# zxuno.net
KiCad netlist of a schematic drawn in EAGLE
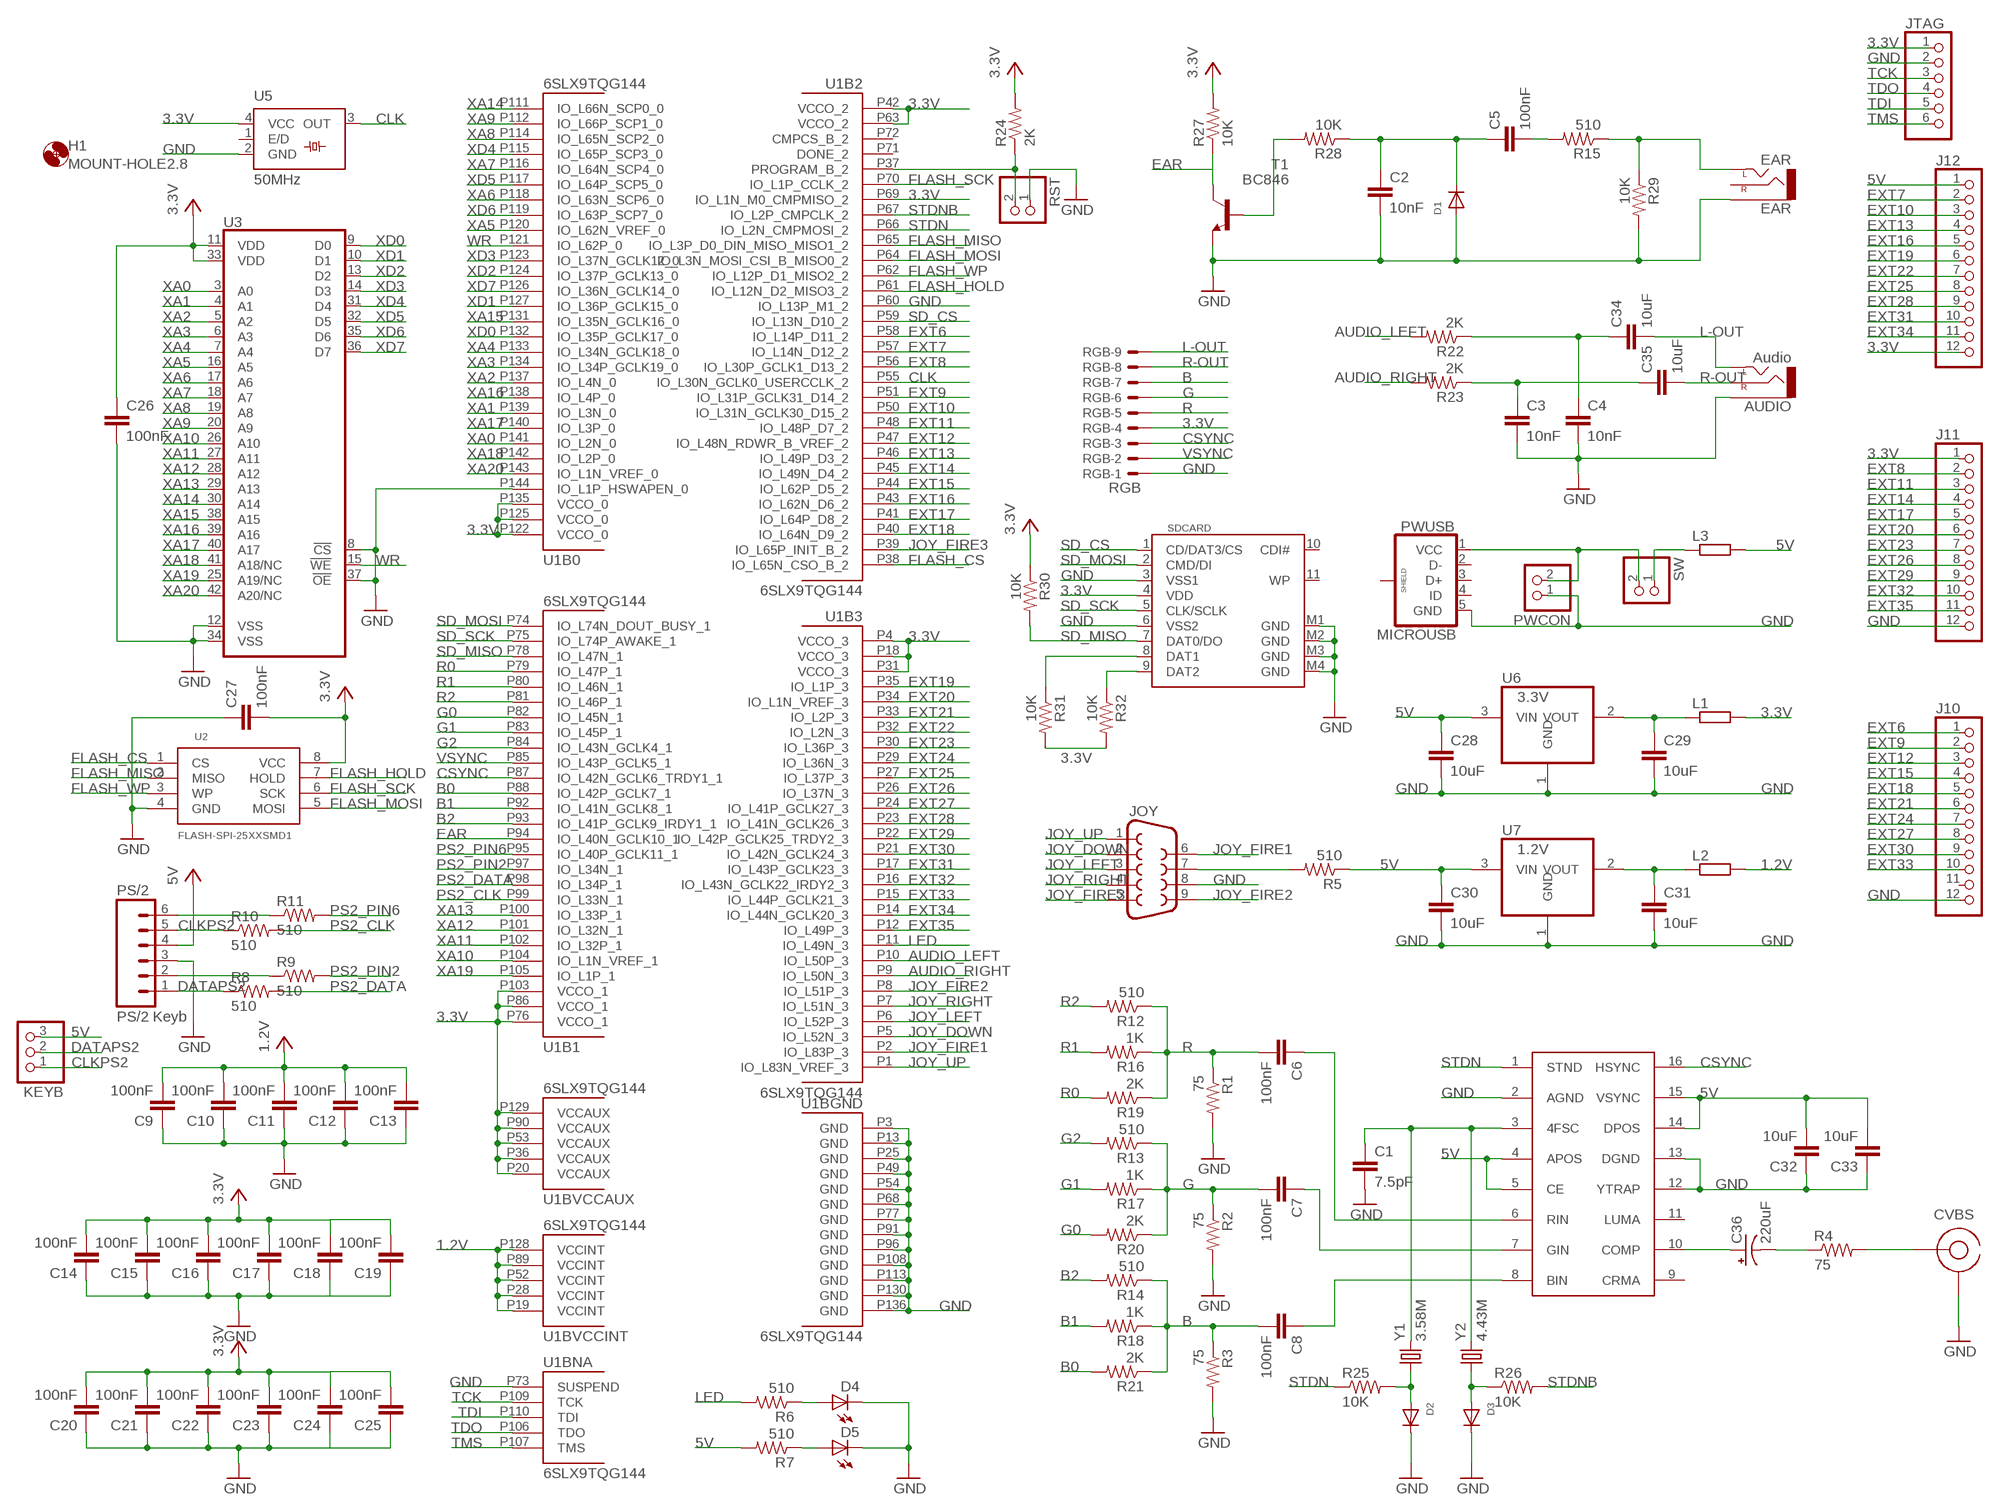
[diagram p0: schematic, sheet 1]

(export (version "E")
  (design (tool "Eeschema 10.0.6"))
  (components
    (comp (ref "AUDIO")
      (value "Audio")
      (footprint "eagle-import:AUDIO-JACK")
      (libsource (lib "eagle-import") (part "AUDIO-JACKPTH"))
    )
    (comp (ref "C1")
      (value "7.5pF")
      (footprint "eagle-import:C0805")
      (libsource (lib "eagle-import") (part "C-EUC0805"))
    )
    (comp (ref "C2")
      (value "10nF")
      (footprint "eagle-import:C0805")
      (libsource (lib "eagle-import") (part "C-EUC0805"))
    )
    (comp (ref "C3")
      (value "10nF")
      (footprint "eagle-import:C0805")
      (libsource (lib "eagle-import") (part "C-EUC0805"))
    )
    (comp (ref "C4")
      (value "10nF")
      (footprint "eagle-import:C0805")
      (libsource (lib "eagle-import") (part "C-EUC0805"))
    )
    (comp (ref "C5")
      (value "100nF")
      (footprint "eagle-import:C0603")
      (libsource (lib "eagle-import") (part "C-EUC0603"))
    )
    (comp (ref "C6")
      (value "100nF")
      (footprint "eagle-import:C0603")
      (libsource (lib "eagle-import") (part "C-EUC0603"))
    )
    (comp (ref "C7")
      (value "100nF")
      (footprint "eagle-import:C0603")
      (libsource (lib "eagle-import") (part "C-EUC0603"))
    )
    (comp (ref "C8")
      (value "100nF")
      (footprint "eagle-import:C0603")
      (libsource (lib "eagle-import") (part "C-EUC0603"))
    )
    (comp (ref "C9")
      (value "100nF")
      (footprint "eagle-import:C0603")
      (libsource (lib "eagle-import") (part "C-EUC0603"))
    )
    (comp (ref "C10")
      (value "100nF")
      (footprint "eagle-import:C0603")
      (libsource (lib "eagle-import") (part "C-EUC0603"))
    )
    (comp (ref "C11")
      (value "100nF")
      (footprint "eagle-import:C0603")
      (libsource (lib "eagle-import") (part "C-EUC0603"))
    )
    (comp (ref "C12")
      (value "100nF")
      (footprint "eagle-import:C0603")
      (libsource (lib "eagle-import") (part "C-EUC0603"))
    )
    (comp (ref "C13")
      (value "100nF")
      (footprint "eagle-import:C0603")
      (libsource (lib "eagle-import") (part "C-EUC0603"))
    )
    (comp (ref "C14")
      (value "100nF")
      (footprint "eagle-import:C0603")
      (libsource (lib "eagle-import") (part "C-EUC0603"))
    )
    (comp (ref "C15")
      (value "100nF")
      (footprint "eagle-import:C0603")
      (libsource (lib "eagle-import") (part "C-EUC0603"))
    )
    (comp (ref "C16")
      (value "100nF")
      (footprint "eagle-import:C0603")
      (libsource (lib "eagle-import") (part "C-EUC0603"))
    )
    (comp (ref "C17")
      (value "100nF")
      (footprint "eagle-import:C0603")
      (libsource (lib "eagle-import") (part "C-EUC0603"))
    )
    (comp (ref "C18")
      (value "100nF")
      (footprint "eagle-import:C0603")
      (libsource (lib "eagle-import") (part "C-EUC0603"))
    )
    (comp (ref "C19")
      (value "100nF")
      (footprint "eagle-import:C0603")
      (libsource (lib "eagle-import") (part "C-EUC0603"))
    )
    (comp (ref "C20")
      (value "100nF")
      (footprint "eagle-import:C0603")
      (libsource (lib "eagle-import") (part "C-EUC0603"))
    )
    (comp (ref "C21")
      (value "100nF")
      (footprint "eagle-import:C0603")
      (libsource (lib "eagle-import") (part "C-EUC0603"))
    )
    (comp (ref "C22")
      (value "100nF")
      (footprint "eagle-import:C0603")
      (libsource (lib "eagle-import") (part "C-EUC0603"))
    )
    (comp (ref "C23")
      (value "100nF")
      (footprint "eagle-import:C0603")
      (libsource (lib "eagle-import") (part "C-EUC0603"))
    )
    (comp (ref "C24")
      (value "100nF")
      (footprint "eagle-import:C0603")
      (libsource (lib "eagle-import") (part "C-EUC0603"))
    )
    (comp (ref "C25")
      (value "100nF")
      (footprint "eagle-import:C0603")
      (libsource (lib "eagle-import") (part "C-EUC0603"))
    )
    (comp (ref "C26")
      (value "100nF")
      (footprint "eagle-import:C0603")
      (libsource (lib "eagle-import") (part "C-EUC0603"))
    )
    (comp (ref "C27")
      (value "100nF")
      (footprint "eagle-import:C0603")
      (libsource (lib "eagle-import") (part "C-EUC0603"))
    )
    (comp (ref "C28")
      (value "10uF")
      (footprint "eagle-import:C0805")
      (libsource (lib "eagle-import") (part "C-EUC0805"))
    )
    (comp (ref "C29")
      (value "10uF")
      (footprint "eagle-import:C0805")
      (libsource (lib "eagle-import") (part "C-EUC0805"))
    )
    (comp (ref "C30")
      (value "10uF")
      (footprint "eagle-import:C0805")
      (libsource (lib "eagle-import") (part "C-EUC0805"))
    )
    (comp (ref "C31")
      (value "10uF")
      (footprint "eagle-import:C0805")
      (libsource (lib "eagle-import") (part "C-EUC0805"))
    )
    (comp (ref "C32")
      (value "10uF")
      (footprint "eagle-import:C0805")
      (libsource (lib "eagle-import") (part "C-EUC0805"))
    )
    (comp (ref "C33")
      (value "10uF")
      (footprint "eagle-import:C0805")
      (libsource (lib "eagle-import") (part "C-EUC0805"))
    )
    (comp (ref "C34")
      (value "10uF")
      (footprint "eagle-import:C0805")
      (libsource (lib "eagle-import") (part "C-EUC0805"))
    )
    (comp (ref "C35")
      (value "10uF")
      (footprint "eagle-import:C0805")
      (libsource (lib "eagle-import") (part "C-EUC0805"))
    )
    (comp (ref "C36")
      (value "220uF")
      (footprint "eagle-import:153CLV-0605")
      (libsource (lib "eagle-import") (part "CPOL-US153CLV-0605"))
    )
    (comp (ref "CVBS")
      (value "RCA")
      (footprint "eagle-import:RCA")
      (libsource (lib "eagle-import") (part "RCA"))
    )
    (comp (ref "D1")
      (value "DIODESOD-323F")
      (footprint "eagle-import:SOD-323F")
      (libsource (lib "eagle-import") (part "DIODESOD-323F"))
    )
    (comp (ref "D2")
      (value "DIODESOD-323F")
      (footprint "eagle-import:SOD-323F")
      (libsource (lib "eagle-import") (part "DIODESOD-323F"))
    )
    (comp (ref "D3")
      (value "DIODESOD-323F")
      (footprint "eagle-import:SOD-323F")
      (libsource (lib "eagle-import") (part "DIODESOD-323F"))
    )
    (comp (ref "D4")
      (value "LEDCHIP-LED0805")
      (footprint "eagle-import:CHIP-LED0805")
      (libsource (lib "eagle-import") (part "LEDCHIP-LED0805"))
    )
    (comp (ref "D5")
      (value "LEDCHIP-LED0805")
      (footprint "eagle-import:CHIP-LED0805")
      (libsource (lib "eagle-import") (part "LEDCHIP-LED0805"))
    )
    (comp (ref "EAR")
      (value "EAR")
      (footprint "eagle-import:AUDIO-JACK")
      (libsource (lib "eagle-import") (part "AUDIO-JACKPTH"))
    )
    (comp (ref "H1")
      (value "MOUNT-HOLE2.8")
      (footprint "eagle-import:2,8")
      (libsource (lib "eagle-import") (part "MOUNT-HOLE2.8"))
    )
    (comp (ref "J10")
      (value "PINHD-1X12")
      (footprint "eagle-import:1X12")
      (libsource (lib "eagle-import") (part "PINHD-1X12"))
    )
    (comp (ref "J11")
      (value "PINHD-1X12")
      (footprint "eagle-import:1X12")
      (libsource (lib "eagle-import") (part "PINHD-1X12"))
    )
    (comp (ref "J12")
      (value "PINHD-1X12")
      (footprint "eagle-import:1X12")
      (libsource (lib "eagle-import") (part "PINHD-1X12"))
    )
    (comp (ref "JOY")
      (value "DB9MALE")
      (footprint "eagle-import:DB9_MALE")
      (libsource (lib "eagle-import") (part "DB9MALE"))
    )
    (comp (ref "JTAG")
      (value "PINHD-1X6")
      (footprint "eagle-import:1X06")
      (libsource (lib "eagle-import") (part "PINHD-1X6"))
    )
    (comp (ref "KEYB")
      (value "PINHD-1X3")
      (footprint "eagle-import:1X03")
      (libsource (lib "eagle-import") (part "PINHD-1X3"))
    )
    (comp (ref "L1")
      (value "R-EU_M0805")
      (footprint "eagle-import:M0805")
      (libsource (lib "eagle-import") (part "R-EU_M0805"))
    )
    (comp (ref "L2")
      (value "R-EU_M0805")
      (footprint "eagle-import:M0805")
      (libsource (lib "eagle-import") (part "R-EU_M0805"))
    )
    (comp (ref "L3")
      (value "R-EU_M0805")
      (footprint "eagle-import:M0805")
      (libsource (lib "eagle-import") (part "R-EU_M0805"))
    )
    (comp (ref "PS/2")
      (value "PS/2 Keyb")
      (footprint "eagle-import:DINC_MIN_TM_6_1PRIMARY")
      (libsource (lib "eagle-import") (part "DINC_MIN_TM_6_1"))
    )
    (comp (ref "PWCON")
      (value "PINHD-1X2")
      (footprint "eagle-import:1X02")
      (libsource (lib "eagle-import") (part "PINHD-1X2"))
    )
    (comp (ref "PWUSB")
      (value "MICROUSB")
      (footprint "eagle-import:MICRO_USB_1PRIMARY")
      (libsource (lib "eagle-import") (part "MICROUSB"))
    )
    (comp (ref "R1")
      (value "75")
      (footprint "eagle-import:M0805")
      (libsource (lib "eagle-import") (part "R-US_M0805"))
    )
    (comp (ref "R2")
      (value "75")
      (footprint "eagle-import:M0805")
      (libsource (lib "eagle-import") (part "R-US_M0805"))
    )
    (comp (ref "R3")
      (value "75")
      (footprint "eagle-import:M0805")
      (libsource (lib "eagle-import") (part "R-US_M0805"))
    )
    (comp (ref "R4")
      (value "75")
      (footprint "eagle-import:M0805")
      (libsource (lib "eagle-import") (part "R-US_M0805"))
    )
    (comp (ref "R5")
      (value "510")
      (footprint "eagle-import:M0805")
      (libsource (lib "eagle-import") (part "R-US_M0805"))
    )
    (comp (ref "R6")
      (value "510")
      (footprint "eagle-import:M0805")
      (libsource (lib "eagle-import") (part "R-US_M0805"))
    )
    (comp (ref "R7")
      (value "510")
      (footprint "eagle-import:M0805")
      (libsource (lib "eagle-import") (part "R-US_M0805"))
    )
    (comp (ref "R8")
      (value "510")
      (footprint "eagle-import:M0805")
      (libsource (lib "eagle-import") (part "R-US_M0805"))
    )
    (comp (ref "R9")
      (value "510")
      (footprint "eagle-import:M0805")
      (libsource (lib "eagle-import") (part "R-US_M0805"))
    )
    (comp (ref "R10")
      (value "510")
      (footprint "eagle-import:M0805")
      (libsource (lib "eagle-import") (part "R-US_M0805"))
    )
    (comp (ref "R11")
      (value "510")
      (footprint "eagle-import:M0805")
      (libsource (lib "eagle-import") (part "R-US_M0805"))
    )
    (comp (ref "R12")
      (value "510")
      (footprint "eagle-import:M0805")
      (libsource (lib "eagle-import") (part "R-US_M0805"))
    )
    (comp (ref "R13")
      (value "510")
      (footprint "eagle-import:M0805")
      (libsource (lib "eagle-import") (part "R-US_M0805"))
    )
    (comp (ref "R14")
      (value "510")
      (footprint "eagle-import:M0805")
      (libsource (lib "eagle-import") (part "R-US_M0805"))
    )
    (comp (ref "R15")
      (value "510")
      (footprint "eagle-import:M0805")
      (libsource (lib "eagle-import") (part "R-US_M0805"))
    )
    (comp (ref "R16")
      (value "1K")
      (footprint "eagle-import:M0805")
      (libsource (lib "eagle-import") (part "R-US_M0805"))
    )
    (comp (ref "R17")
      (value "1K")
      (footprint "eagle-import:M0805")
      (libsource (lib "eagle-import") (part "R-US_M0805"))
    )
    (comp (ref "R18")
      (value "1K")
      (footprint "eagle-import:M0805")
      (libsource (lib "eagle-import") (part "R-US_M0805"))
    )
    (comp (ref "R19")
      (value "2K")
      (footprint "eagle-import:M0805")
      (libsource (lib "eagle-import") (part "R-US_M0805"))
    )
    (comp (ref "R20")
      (value "2K")
      (footprint "eagle-import:M0805")
      (libsource (lib "eagle-import") (part "R-US_M0805"))
    )
    (comp (ref "R21")
      (value "2K")
      (footprint "eagle-import:M0805")
      (libsource (lib "eagle-import") (part "R-US_M0805"))
    )
    (comp (ref "R22")
      (value "2K")
      (footprint "eagle-import:M0805")
      (libsource (lib "eagle-import") (part "R-US_M0805"))
    )
    (comp (ref "R23")
      (value "2K")
      (footprint "eagle-import:M0805")
      (libsource (lib "eagle-import") (part "R-US_M0805"))
    )
    (comp (ref "R24")
      (value "2K")
      (footprint "eagle-import:M0805")
      (libsource (lib "eagle-import") (part "R-US_M0805"))
    )
    (comp (ref "R25")
      (value "10K")
      (footprint "eagle-import:M0805")
      (libsource (lib "eagle-import") (part "R-US_M0805"))
    )
    (comp (ref "R26")
      (value "10K")
      (footprint "eagle-import:M0805")
      (libsource (lib "eagle-import") (part "R-US_M0805"))
    )
    (comp (ref "R27")
      (value "10K")
      (footprint "eagle-import:M0805")
      (libsource (lib "eagle-import") (part "R-US_M0805"))
    )
    (comp (ref "R28")
      (value "10K")
      (footprint "eagle-import:M0805")
      (libsource (lib "eagle-import") (part "R-US_M0805"))
    )
    (comp (ref "R29")
      (value "10K")
      (footprint "eagle-import:M0805")
      (libsource (lib "eagle-import") (part "R-US_M0805"))
    )
    (comp (ref "R30")
      (value "10K")
      (footprint "eagle-import:M0805")
      (libsource (lib "eagle-import") (part "R-US_M0805"))
    )
    (comp (ref "R31")
      (value "10K")
      (footprint "eagle-import:M0805")
      (libsource (lib "eagle-import") (part "R-US_M0805"))
    )
    (comp (ref "R32")
      (value "10K")
      (footprint "eagle-import:M0805")
      (libsource (lib "eagle-import") (part "R-US_M0805"))
    )
    (comp (ref "RGB")
      (value "RGB")
      (footprint "eagle-import:53048-09")
      (fields (field (name "MPN") "53048-0910"))
      (libsource (lib "eagle-import") (part "53?-09048"))
    )
    (comp (ref "RST")
      (value "PINHD-1X2")
      (footprint "eagle-import:1X02")
      (libsource (lib "eagle-import") (part "PINHD-1X2"))
    )
    (comp (ref "SDCARD")
      (value "SDCARD")
      (footprint "eagle-import:SDCMF-10915W010")
      (libsource (lib "eagle-import") (part "SDCARD"))
    )
    (comp (ref "SW")
      (value "PINHD-1X2")
      (footprint "eagle-import:1X02")
      (libsource (lib "eagle-import") (part "PINHD-1X2"))
    )
    (comp (ref "T1")
      (value "BC846")
      (footprint "eagle-import:SOT23")
      (libsource (lib "eagle-import") (part "BC846"))
    )
    (comp (ref "U1")
      (value "6SLX9TQG144")
      (footprint "eagle-import:TQ144")
      (libsource (lib "eagle-import") (part "6SLX9TQG144"))
    )
    (comp (ref "U2")
      (value "FLASH-SPI-25XXSMD1")
      (footprint "eagle-import:SO08-EIAJ")
      (libsource (lib "eagle-import") (part "FLASH-SPI-25XXSMD1"))
    )
    (comp (ref "U3")
      (value "ISSI_SRAM_8BIT")
      (footprint "eagle-import:TSOP44-II")
      (libsource (lib "eagle-import") (part "ISSI_SRAM_8BIT"))
    )
    (comp (ref "U4")
      (value "AD724")
      (footprint "eagle-import:SO16W")
      (libsource (lib "eagle-import") (part "AD725"))
    )
    (comp (ref "U5")
      (value "50MHz")
      (footprint "eagle-import:SM_OSC_1PRIMARY")
      (libsource (lib "eagle-import") (part "SM_OSC_1"))
    )
    (comp (ref "U6")
      (value "3.3V")
      (footprint "eagle-import:SOT223")
      (fields (field (name "MPN") "REG1117"))
      (libsource (lib "eagle-import") (part "REG1117"))
    )
    (comp (ref "U7")
      (value "1.2V")
      (footprint "eagle-import:SOT223")
      (fields (field (name "MPN") "REG1117"))
      (libsource (lib "eagle-import") (part "REG1117"))
    )
    (comp (ref "Y1")
      (value "3.58M")
      (footprint "eagle-import:HC49UP")
      (libsource (lib "eagle-import") (part "CRYSTALHC49UP"))
    )
    (comp (ref "Y2")
      (value "4.43M")
      (footprint "eagle-import:HC49UP")
      (libsource (lib "eagle-import") (part "CRYSTALHC49UP"))
    )
  )
  (nets
    (net (code "1") (name "/AUDIO_LEFT") (class "Default")
      (node (ref "R22") (pin "2") (pinfunction "2_2") (pintype "passive"))
      (node (ref "U1") (pin "P10") (pinfunction "IO_L50P_3_P10") (pintype "bidirectional"))
    )
    (net (code "2") (name "/AUDIO_RIGHT") (class "Default")
      (node (ref "R23") (pin "2") (pinfunction "2_2") (pintype "passive"))
      (node (ref "U1") (pin "P9") (pinfunction "IO_L50N_3_P9") (pintype "bidirectional"))
    )
    (net (code "3") (name "/B") (class "Default")
      (node (ref "C8") (pin "2") (pinfunction "2_2") (pintype "passive"))
      (node (ref "R14") (pin "1") (pinfunction "1_1") (pintype "passive"))
      (node (ref "R18") (pin "1") (pinfunction "1_1") (pintype "passive"))
      (node (ref "R21") (pin "1") (pinfunction "1_1") (pintype "passive"))
      (node (ref "R3") (pin "1") (pinfunction "1_1") (pintype "passive"))
      (node (ref "RGB") (pin "7") (pinfunction "S_7") (pintype "passive"))
    )
    (net (code "4") (name "/B0") (class "Default")
      (node (ref "R21") (pin "2") (pinfunction "2_2") (pintype "passive"))
      (node (ref "U1") (pin "P88") (pinfunction "IO_L42P_GCLK7_1_P88") (pintype "bidirectional"))
    )
    (net (code "5") (name "/B1") (class "Default")
      (node (ref "R18") (pin "2") (pinfunction "2_2") (pintype "passive"))
      (node (ref "U1") (pin "P92") (pinfunction "IO_L41N_GCLK8_1_P92") (pintype "bidirectional"))
    )
    (net (code "6") (name "/B2") (class "Default")
      (node (ref "R14") (pin "2") (pinfunction "2_2") (pintype "passive"))
      (node (ref "U1") (pin "P93") (pinfunction "IO_L41P_GCLK9_IRDY1_1_P93") (pintype "bidirectional"))
    )
    (net (code "7") (name "/CLK") (class "Default")
      (node (ref "U1") (pin "P55") (pinfunction "IO_L30N_GCLK0_USERCCLK_2_P55") (pintype "bidirectional"))
      (node (ref "U5") (pin "3") (pinfunction "OUT_3") (pintype "output"))
    )
    (net (code "8") (name "/CLKPS2") (class "Default")
      (node (ref "KEYB") (pin "1") (pinfunction "1_1") (pintype "passive"))
      (node (ref "PS/2") (pin "5") (pinfunction "5_5") (pintype "passive"))
      (node (ref "R10") (pin "1") (pinfunction "1_1") (pintype "passive"))
    )
    (net (code "9") (name "/CSYNC") (class "Default")
      (node (ref "RGB") (pin "3") (pinfunction "S_3") (pintype "passive"))
      (node (ref "U1") (pin "P87") (pinfunction "IO_L42N_GCLK6_TRDY1_1_P87") (pintype "bidirectional"))
      (node (ref "U4") (pin "16") (pinfunction "HSYNC_16") (pintype "bidirectional"))
    )
    (net (code "10") (name "/DATAPS2") (class "Default")
      (node (ref "KEYB") (pin "2") (pinfunction "2_2") (pintype "passive"))
      (node (ref "PS/2") (pin "1") (pinfunction "1_1") (pintype "passive"))
      (node (ref "R8") (pin "1") (pinfunction "1_1") (pintype "passive"))
    )
    (net (code "11") (name "/EAR") (class "Default")
      (node (ref "R27") (pin "1") (pinfunction "1_1") (pintype "passive"))
      (node (ref "T1") (pin "3") (pinfunction "C_3") (pintype "passive"))
      (node (ref "U1") (pin "P94") (pinfunction "IO_L40N_GCLK10_1_P94") (pintype "bidirectional"))
    )
    (net (code "12") (name "/EXT6") (class "Default")
      (node (ref "J10") (pin "1") (pinfunction "1_1") (pintype "passive"))
      (node (ref "U1") (pin "P58") (pinfunction "IO_L14P_D11_2_P58") (pintype "bidirectional"))
    )
    (net (code "13") (name "/EXT7") (class "Default")
      (node (ref "J12") (pin "2") (pinfunction "2_2") (pintype "passive"))
      (node (ref "U1") (pin "P57") (pinfunction "IO_L14N_D12_2_P57") (pintype "bidirectional"))
    )
    (net (code "14") (name "/EXT8") (class "Default")
      (node (ref "J11") (pin "2") (pinfunction "2_2") (pintype "passive"))
      (node (ref "U1") (pin "P56") (pinfunction "IO_L30P_GCLK1_D13_2_P56") (pintype "bidirectional"))
    )
    (net (code "15") (name "/EXT9") (class "Default")
      (node (ref "J10") (pin "2") (pinfunction "2_2") (pintype "passive"))
      (node (ref "U1") (pin "P51") (pinfunction "IO_L31P_GCLK31_D14_2_P51") (pintype "bidirectional"))
    )
    (net (code "16") (name "/EXT10") (class "Default")
      (node (ref "J12") (pin "3") (pinfunction "3_3") (pintype "passive"))
      (node (ref "U1") (pin "P50") (pinfunction "IO_L31N_GCLK30_D15_2_P50") (pintype "bidirectional"))
    )
    (net (code "17") (name "/EXT11") (class "Default")
      (node (ref "J11") (pin "3") (pinfunction "3_3") (pintype "passive"))
      (node (ref "U1") (pin "P48") (pinfunction "IO_L48P_D7_2_P48") (pintype "bidirectional"))
    )
    (net (code "18") (name "/EXT12") (class "Default")
      (node (ref "J10") (pin "3") (pinfunction "3_3") (pintype "passive"))
      (node (ref "U1") (pin "P47") (pinfunction "IO_L48N_RDWR_B_VREF_2_P47") (pintype "bidirectional"))
    )
    (net (code "19") (name "/EXT13") (class "Default")
      (node (ref "J12") (pin "4") (pinfunction "4_4") (pintype "passive"))
      (node (ref "U1") (pin "P46") (pinfunction "IO_L49P_D3_2_P46") (pintype "bidirectional"))
    )
    (net (code "20") (name "/EXT14") (class "Default")
      (node (ref "J11") (pin "4") (pinfunction "4_4") (pintype "passive"))
      (node (ref "U1") (pin "P45") (pinfunction "IO_L49N_D4_2_P45") (pintype "bidirectional"))
    )
    (net (code "21") (name "/EXT15") (class "Default")
      (node (ref "J10") (pin "4") (pinfunction "4_4") (pintype "passive"))
      (node (ref "U1") (pin "P44") (pinfunction "IO_L62P_D5_2_P44") (pintype "bidirectional"))
    )
    (net (code "22") (name "/EXT16") (class "Default")
      (node (ref "J12") (pin "5") (pinfunction "5_5") (pintype "passive"))
      (node (ref "U1") (pin "P43") (pinfunction "IO_L62N_D6_2_P43") (pintype "bidirectional"))
    )
    (net (code "23") (name "/EXT17") (class "Default")
      (node (ref "J11") (pin "5") (pinfunction "5_5") (pintype "passive"))
      (node (ref "U1") (pin "P41") (pinfunction "IO_L64P_D8_2_P41") (pintype "bidirectional"))
    )
    (net (code "24") (name "/EXT18") (class "Default")
      (node (ref "J10") (pin "5") (pinfunction "5_5") (pintype "passive"))
      (node (ref "U1") (pin "P40") (pinfunction "IO_L64N_D9_2_P40") (pintype "bidirectional"))
    )
    (net (code "25") (name "/EXT19") (class "Default")
      (node (ref "J12") (pin "6") (pinfunction "6_6") (pintype "passive"))
      (node (ref "U1") (pin "P35") (pinfunction "IO_L1P_3_P35") (pintype "bidirectional"))
    )
    (net (code "26") (name "/EXT20") (class "Default")
      (node (ref "J11") (pin "6") (pinfunction "6_6") (pintype "passive"))
      (node (ref "U1") (pin "P34") (pinfunction "IO_L1N_VREF_3_P34") (pintype "bidirectional"))
    )
    (net (code "27") (name "/EXT21") (class "Default")
      (node (ref "J10") (pin "6") (pinfunction "6_6") (pintype "passive"))
      (node (ref "U1") (pin "P33") (pinfunction "IO_L2P_3_P33") (pintype "bidirectional"))
    )
    (net (code "28") (name "/EXT22") (class "Default")
      (node (ref "J12") (pin "7") (pinfunction "7_7") (pintype "passive"))
      (node (ref "U1") (pin "P32") (pinfunction "IO_L2N_3_P32") (pintype "bidirectional"))
    )
    (net (code "29") (name "/EXT23") (class "Default")
      (node (ref "J11") (pin "7") (pinfunction "7_7") (pintype "passive"))
      (node (ref "U1") (pin "P30") (pinfunction "IO_L36P_3_P30") (pintype "bidirectional"))
    )
    (net (code "30") (name "/EXT24") (class "Default")
      (node (ref "J10") (pin "7") (pinfunction "7_7") (pintype "passive"))
      (node (ref "U1") (pin "P29") (pinfunction "IO_L36N_3_P29") (pintype "bidirectional"))
    )
    (net (code "31") (name "/EXT25") (class "Default")
      (node (ref "J12") (pin "8") (pinfunction "8_8") (pintype "passive"))
      (node (ref "U1") (pin "P27") (pinfunction "IO_L37P_3_P27") (pintype "bidirectional"))
    )
    (net (code "32") (name "/EXT26") (class "Default")
      (node (ref "J11") (pin "8") (pinfunction "8_8") (pintype "passive"))
      (node (ref "U1") (pin "P26") (pinfunction "IO_L37N_3_P26") (pintype "bidirectional"))
    )
    (net (code "33") (name "/EXT27") (class "Default")
      (node (ref "J10") (pin "8") (pinfunction "8_8") (pintype "passive"))
      (node (ref "U1") (pin "P24") (pinfunction "IO_L41P_GCLK27_3_P24") (pintype "bidirectional"))
    )
    (net (code "34") (name "/EXT28") (class "Default")
      (node (ref "J12") (pin "9") (pinfunction "9_9") (pintype "passive"))
      (node (ref "U1") (pin "P23") (pinfunction "IO_L41N_GCLK26_3_P23") (pintype "bidirectional"))
    )
    (net (code "35") (name "/EXT29") (class "Default")
      (node (ref "J11") (pin "9") (pinfunction "9_9") (pintype "passive"))
      (node (ref "U1") (pin "P22") (pinfunction "IO_L42P_GCLK25_TRDY2_3_P22") (pintype "bidirectional"))
    )
    (net (code "36") (name "/EXT30") (class "Default")
      (node (ref "J10") (pin "9") (pinfunction "9_9") (pintype "passive"))
      (node (ref "U1") (pin "P21") (pinfunction "IO_L42N_GCLK24_3_P21") (pintype "bidirectional"))
    )
    (net (code "37") (name "/EXT31") (class "Default")
      (node (ref "J12") (pin "10") (pinfunction "10_10") (pintype "passive"))
      (node (ref "U1") (pin "P17") (pinfunction "IO_L43P_GCLK23_3_P17") (pintype "bidirectional"))
    )
    (net (code "38") (name "/EXT32") (class "Default")
      (node (ref "J11") (pin "10") (pinfunction "10_10") (pintype "passive"))
      (node (ref "U1") (pin "P16") (pinfunction "IO_L43N_GCLK22_IRDY2_3_P16") (pintype "bidirectional"))
    )
    (net (code "39") (name "/EXT33") (class "Default")
      (node (ref "J10") (pin "10") (pinfunction "10_10") (pintype "passive"))
      (node (ref "U1") (pin "P15") (pinfunction "IO_L44P_GCLK21_3_P15") (pintype "bidirectional"))
    )
    (net (code "40") (name "/EXT34") (class "Default")
      (node (ref "J12") (pin "11") (pinfunction "11_11") (pintype "passive"))
      (node (ref "U1") (pin "P14") (pinfunction "IO_L44N_GCLK20_3_P14") (pintype "bidirectional"))
    )
    (net (code "41") (name "/EXT35") (class "Default")
      (node (ref "J11") (pin "11") (pinfunction "11_11") (pintype "passive"))
      (node (ref "U1") (pin "P12") (pinfunction "IO_L49P_3_P12") (pintype "bidirectional"))
    )
    (net (code "42") (name "/FLASH_CS") (class "Default")
      (node (ref "U1") (pin "P38") (pinfunction "IO_L65N_CSO_B_2_P38") (pintype "bidirectional"))
      (node (ref "U2") (pin "1") (pinfunction "CS_1") (pintype "bidirectional"))
    )
    (net (code "43") (name "/FLASH_HOLD") (class "Default")
      (node (ref "U1") (pin "P61") (pinfunction "IO_L12N_D2_MISO3_2_P61") (pintype "bidirectional"))
      (node (ref "U2") (pin "7") (pinfunction "HOLD_7") (pintype "bidirectional"))
    )
    (net (code "44") (name "/FLASH_MISO") (class "Default")
      (node (ref "U1") (pin "P65") (pinfunction "IO_L3P_D0_DIN_MISO_MISO1_2_P65") (pintype "bidirectional"))
      (node (ref "U2") (pin "2") (pinfunction "MISO_2") (pintype "bidirectional"))
    )
    (net (code "45") (name "/FLASH_MOSI") (class "Default")
      (node (ref "U1") (pin "P64") (pinfunction "IO_L3N_MOSI_CSI_B_MISO0_2_P64") (pintype "bidirectional"))
      (node (ref "U2") (pin "5") (pinfunction "MOSI_5") (pintype "bidirectional"))
    )
    (net (code "46") (name "/FLASH_SCK") (class "Default")
      (node (ref "U1") (pin "P70") (pinfunction "IO_L1P_CCLK_2_P70") (pintype "bidirectional"))
      (node (ref "U2") (pin "6") (pinfunction "SCK_6") (pintype "bidirectional"))
    )
    (net (code "47") (name "/FLASH_WP") (class "Default")
      (node (ref "U1") (pin "P62") (pinfunction "IO_L12P_D1_MISO2_2_P62") (pintype "bidirectional"))
      (node (ref "U2") (pin "3") (pinfunction "WP_3") (pintype "bidirectional"))
    )
    (net (code "48") (name "/G") (class "Default")
      (node (ref "C7") (pin "2") (pinfunction "2_2") (pintype "passive"))
      (node (ref "R13") (pin "1") (pinfunction "1_1") (pintype "passive"))
      (node (ref "R17") (pin "1") (pinfunction "1_1") (pintype "passive"))
      (node (ref "R2") (pin "1") (pinfunction "1_1") (pintype "passive"))
      (node (ref "R20") (pin "1") (pinfunction "1_1") (pintype "passive"))
      (node (ref "RGB") (pin "6") (pinfunction "S_6") (pintype "passive"))
    )
    (net (code "49") (name "/G0") (class "Default")
      (node (ref "R20") (pin "2") (pinfunction "2_2") (pintype "passive"))
      (node (ref "U1") (pin "P82") (pinfunction "IO_L45N_1_P82") (pintype "bidirectional"))
    )
    (net (code "50") (name "/G1") (class "Default")
      (node (ref "R17") (pin "2") (pinfunction "2_2") (pintype "passive"))
      (node (ref "U1") (pin "P83") (pinfunction "IO_L45P_1_P83") (pintype "bidirectional"))
    )
    (net (code "51") (name "/G2") (class "Default")
      (node (ref "R13") (pin "2") (pinfunction "2_2") (pintype "passive"))
      (node (ref "U1") (pin "P84") (pinfunction "IO_L43N_GCLK4_1_P84") (pintype "bidirectional"))
    )
    (net (code "52") (name "/JOY_DOWN") (class "Default")
      (node (ref "JOY") (pin "2") (pinfunction "2_2") (pintype "passive"))
      (node (ref "U1") (pin "P5") (pinfunction "IO_L52N_3_P5") (pintype "bidirectional"))
    )
    (net (code "53") (name "/JOY_FIRE1") (class "Default")
      (node (ref "JOY") (pin "6") (pinfunction "6_6") (pintype "passive"))
      (node (ref "U1") (pin "P2") (pinfunction "IO_L83P_3_P2") (pintype "bidirectional"))
    )
    (net (code "54") (name "/JOY_FIRE2") (class "Default")
      (node (ref "JOY") (pin "9") (pinfunction "9_9") (pintype "passive"))
      (node (ref "U1") (pin "P8") (pinfunction "IO_L51P_3_P8") (pintype "bidirectional"))
    )
    (net (code "55") (name "/JOY_FIRE3") (class "Default")
      (node (ref "JOY") (pin "5") (pinfunction "5_5") (pintype "passive"))
      (node (ref "U1") (pin "P39") (pinfunction "IO_L65P_INIT_B_2_P39") (pintype "bidirectional"))
    )
    (net (code "56") (name "/JOY_LEFT") (class "Default")
      (node (ref "JOY") (pin "3") (pinfunction "3_3") (pintype "passive"))
      (node (ref "U1") (pin "P6") (pinfunction "IO_L52P_3_P6") (pintype "bidirectional"))
    )
    (net (code "57") (name "/JOY_RIGHT") (class "Default")
      (node (ref "JOY") (pin "4") (pinfunction "4_4") (pintype "passive"))
      (node (ref "U1") (pin "P7") (pinfunction "IO_L51N_3_P7") (pintype "bidirectional"))
    )
    (net (code "58") (name "/JOY_UP") (class "Default")
      (node (ref "JOY") (pin "1") (pinfunction "1_1") (pintype "passive"))
      (node (ref "U1") (pin "P1") (pinfunction "IO_L83N_VREF_3_P1") (pintype "bidirectional"))
    )
    (net (code "59") (name "/L-OUT") (class "Default")
      (node (ref "AUDIO") (pin "TIP") (pinfunction "LEFT_TIP") (pintype "bidirectional"))
      (node (ref "C34") (pin "2") (pinfunction "2_2") (pintype "passive"))
      (node (ref "RGB") (pin "9") (pinfunction "S_9") (pintype "passive"))
    )
    (net (code "60") (name "/LED") (class "Default")
      (node (ref "R6") (pin "2") (pinfunction "2_2") (pintype "passive"))
      (node (ref "U1") (pin "P11") (pinfunction "IO_L49N_3_P11") (pintype "bidirectional"))
    )
    (net (code "61") (name "/PS2_CLK") (class "Default")
      (node (ref "R10") (pin "2") (pinfunction "2_2") (pintype "passive"))
      (node (ref "U1") (pin "P99") (pinfunction "IO_L33N_1_P99") (pintype "bidirectional"))
    )
    (net (code "62") (name "/PS2_DATA") (class "Default")
      (node (ref "R8") (pin "2") (pinfunction "2_2") (pintype "passive"))
      (node (ref "U1") (pin "P98") (pinfunction "IO_L34P_1_P98") (pintype "bidirectional"))
    )
    (net (code "63") (name "/PS2_PIN2") (class "Default")
      (node (ref "R9") (pin "2") (pinfunction "2_2") (pintype "passive"))
      (node (ref "U1") (pin "P97") (pinfunction "IO_L34N_1_P97") (pintype "bidirectional"))
    )
    (net (code "64") (name "/PS2_PIN6") (class "Default")
      (node (ref "R11") (pin "2") (pinfunction "2_2") (pintype "passive"))
      (node (ref "U1") (pin "P95") (pinfunction "IO_L40P_GCLK11_1_P95") (pintype "bidirectional"))
    )
    (net (code "65") (name "/R") (class "Default")
      (node (ref "C6") (pin "2") (pinfunction "2_2") (pintype "passive"))
      (node (ref "R1") (pin "1") (pinfunction "1_1") (pintype "passive"))
      (node (ref "R12") (pin "1") (pinfunction "1_1") (pintype "passive"))
      (node (ref "R16") (pin "1") (pinfunction "1_1") (pintype "passive"))
      (node (ref "R19") (pin "1") (pinfunction "1_1") (pintype "passive"))
      (node (ref "RGB") (pin "5") (pinfunction "S_5") (pintype "passive"))
    )
    (net (code "66") (name "/R-OUT") (class "Default")
      (node (ref "AUDIO") (pin "RING") (pinfunction "RIGHT_RING") (pintype "bidirectional"))
      (node (ref "C35") (pin "2") (pinfunction "2_2") (pintype "passive"))
      (node (ref "RGB") (pin "8") (pinfunction "S_8") (pintype "passive"))
    )
    (net (code "67") (name "/R0") (class "Default")
      (node (ref "R19") (pin "2") (pinfunction "2_2") (pintype "passive"))
      (node (ref "U1") (pin "P79") (pinfunction "IO_L47P_1_P79") (pintype "bidirectional"))
    )
    (net (code "68") (name "/R1") (class "Default")
      (node (ref "R16") (pin "2") (pinfunction "2_2") (pintype "passive"))
      (node (ref "U1") (pin "P80") (pinfunction "IO_L46N_1_P80") (pintype "bidirectional"))
    )
    (net (code "69") (name "/R2") (class "Default")
      (node (ref "R12") (pin "2") (pinfunction "2_2") (pintype "passive"))
      (node (ref "U1") (pin "P81") (pinfunction "IO_L46P_1_P81") (pintype "bidirectional"))
    )
    (net (code "70") (name "/SD_CS") (class "Default")
      (node (ref "SDCARD") (pin "1") (pinfunction "CD/DAT3/CS_1") (pintype "bidirectional"))
      (node (ref "U1") (pin "P59") (pinfunction "IO_L13N_D10_2_P59") (pintype "bidirectional"))
    )
    (net (code "71") (name "/SD_MISO") (class "Default")
      (node (ref "R30") (pin "2") (pinfunction "2_2") (pintype "passive"))
      (node (ref "SDCARD") (pin "7") (pinfunction "DAT0/DO_7") (pintype "bidirectional"))
      (node (ref "U1") (pin "P78") (pinfunction "IO_L47N_1_P78") (pintype "bidirectional"))
    )
    (net (code "72") (name "/SD_MOSI") (class "Default")
      (node (ref "SDCARD") (pin "2") (pinfunction "CMD/DI_2") (pintype "bidirectional"))
      (node (ref "U1") (pin "P74") (pinfunction "IO_L74N_DOUT_BUSY_1_P74") (pintype "bidirectional"))
    )
    (net (code "73") (name "/SD_SCK") (class "Default")
      (node (ref "SDCARD") (pin "5") (pinfunction "CLK/SCLK_5") (pintype "bidirectional"))
      (node (ref "U1") (pin "P75") (pinfunction "IO_L74P_AWAKE_1_P75") (pintype "bidirectional"))
    )
    (net (code "74") (name "/STDN") (class "Default")
      (node (ref "R25") (pin "1") (pinfunction "1_1") (pintype "passive"))
      (node (ref "U1") (pin "P66") (pinfunction "IO_L2N_CMPMOSI_2_P66") (pintype "bidirectional"))
      (node (ref "U4") (pin "1") (pinfunction "STND_1") (pintype "bidirectional"))
    )
    (net (code "75") (name "/STDNB") (class "Default")
      (node (ref "R26") (pin "2") (pinfunction "2_2") (pintype "passive"))
      (node (ref "U1") (pin "P67") (pinfunction "IO_L2P_CMPCLK_2_P67") (pintype "bidirectional"))
    )
    (net (code "76") (name "/TCK") (class "Default")
      (node (ref "JTAG") (pin "3") (pinfunction "3_3") (pintype "passive"))
      (node (ref "U1") (pin "P109") (pinfunction "TCK_P109") (pintype "input"))
    )
    (net (code "77") (name "/TDI") (class "Default")
      (node (ref "JTAG") (pin "5") (pinfunction "5_5") (pintype "passive"))
      (node (ref "U1") (pin "P110") (pinfunction "TDI_P110") (pintype "input"))
    )
    (net (code "78") (name "/TDO") (class "Default")
      (node (ref "JTAG") (pin "4") (pinfunction "4_4") (pintype "passive"))
      (node (ref "U1") (pin "P106") (pinfunction "TDO_P106") (pintype "output"))
    )
    (net (code "79") (name "/TMS") (class "Default")
      (node (ref "JTAG") (pin "6") (pinfunction "6_6") (pintype "passive"))
      (node (ref "U1") (pin "P107") (pinfunction "TMS_P107") (pintype "input"))
    )
    (net (code "80") (name "/VSYNC") (class "Default")
      (node (ref "RGB") (pin "2") (pinfunction "S_2") (pintype "passive"))
      (node (ref "U1") (pin "P85") (pinfunction "IO_L43P_GCLK5_1_P85") (pintype "bidirectional"))
    )
    (net (code "81") (name "/WR") (class "Default")
      (node (ref "U1") (pin "P121") (pinfunction "IO_L62P_0_P121") (pintype "bidirectional"))
      (node (ref "U3") (pin "15") (pinfunction "~{WE}_15") (pintype "input"))
    )
    (net (code "82") (name "/XA0") (class "Default")
      (node (ref "U1") (pin "P141") (pinfunction "IO_L2N_0_P141") (pintype "bidirectional"))
      (node (ref "U3") (pin "3") (pinfunction "A0_3") (pintype "input"))
    )
    (net (code "83") (name "/XA1") (class "Default")
      (node (ref "U1") (pin "P139") (pinfunction "IO_L3N_0_P139") (pintype "bidirectional"))
      (node (ref "U3") (pin "4") (pinfunction "A1_4") (pintype "input"))
    )
    (net (code "84") (name "/XA2") (class "Default")
      (node (ref "U1") (pin "P137") (pinfunction "IO_L4N_0_P137") (pintype "bidirectional"))
      (node (ref "U3") (pin "5") (pinfunction "A2_5") (pintype "input"))
    )
    (net (code "85") (name "/XA3") (class "Default")
      (node (ref "U1") (pin "P134") (pinfunction "IO_L34P_GCLK19_0_P134") (pintype "bidirectional"))
      (node (ref "U3") (pin "6") (pinfunction "A3_6") (pintype "input"))
    )
    (net (code "86") (name "/XA4") (class "Default")
      (node (ref "U1") (pin "P133") (pinfunction "IO_L34N_GCLK18_0_P133") (pintype "bidirectional"))
      (node (ref "U3") (pin "7") (pinfunction "A4_7") (pintype "input"))
    )
    (net (code "87") (name "/XA5") (class "Default")
      (node (ref "U1") (pin "P120") (pinfunction "IO_L62N_VREF_0_P120") (pintype "bidirectional"))
      (node (ref "U3") (pin "16") (pinfunction "A5_16") (pintype "input"))
    )
    (net (code "88") (name "/XA6") (class "Default")
      (node (ref "U1") (pin "P118") (pinfunction "IO_L63N_SCP6_0_P118") (pintype "bidirectional"))
      (node (ref "U3") (pin "17") (pinfunction "A6_17") (pintype "input"))
    )
    (net (code "89") (name "/XA7") (class "Default")
      (node (ref "U1") (pin "P116") (pinfunction "IO_L64N_SCP4_0_P116") (pintype "bidirectional"))
      (node (ref "U3") (pin "18") (pinfunction "A7_18") (pintype "input"))
    )
    (net (code "90") (name "/XA8") (class "Default")
      (node (ref "U1") (pin "P114") (pinfunction "IO_L65N_SCP2_0_P114") (pintype "bidirectional"))
      (node (ref "U3") (pin "19") (pinfunction "A8_19") (pintype "input"))
    )
    (net (code "91") (name "/XA9") (class "Default")
      (node (ref "U1") (pin "P112") (pinfunction "IO_L66P_SCP1_0_P112") (pintype "bidirectional"))
      (node (ref "U3") (pin "20") (pinfunction "A9_20") (pintype "input"))
    )
    (net (code "92") (name "/XA10") (class "Default")
      (node (ref "U1") (pin "P104") (pinfunction "IO_L1N_VREF_1_P104") (pintype "bidirectional"))
      (node (ref "U3") (pin "26") (pinfunction "A10_26") (pintype "input"))
    )
    (net (code "93") (name "/XA11") (class "Default")
      (node (ref "U1") (pin "P102") (pinfunction "IO_L32P_1_P102") (pintype "bidirectional"))
      (node (ref "U3") (pin "27") (pinfunction "A11_27") (pintype "input"))
    )
    (net (code "94") (name "/XA12") (class "Default")
      (node (ref "U1") (pin "P101") (pinfunction "IO_L32N_1_P101") (pintype "bidirectional"))
      (node (ref "U3") (pin "28") (pinfunction "A12_28") (pintype "input"))
    )
    (net (code "95") (name "/XA13") (class "Default")
      (node (ref "U1") (pin "P100") (pinfunction "IO_L33P_1_P100") (pintype "bidirectional"))
      (node (ref "U3") (pin "29") (pinfunction "A13_29") (pintype "input"))
    )
    (net (code "96") (name "/XA14") (class "Default")
      (node (ref "U1") (pin "P111") (pinfunction "IO_L66N_SCP0_0_P111") (pintype "bidirectional"))
      (node (ref "U3") (pin "30") (pinfunction "A14_30") (pintype "input"))
    )
    (net (code "97") (name "/XA15") (class "Default")
      (node (ref "U1") (pin "P131") (pinfunction "IO_L35N_GCLK16_0_P131") (pintype "bidirectional"))
      (node (ref "U3") (pin "38") (pinfunction "A15_38") (pintype "input"))
    )
    (net (code "98") (name "/XA16") (class "Default")
      (node (ref "U1") (pin "P138") (pinfunction "IO_L4P_0_P138") (pintype "bidirectional"))
      (node (ref "U3") (pin "39") (pinfunction "A16_39") (pintype "input"))
    )
    (net (code "99") (name "/XA17") (class "Default")
      (node (ref "U1") (pin "P140") (pinfunction "IO_L3P_0_P140") (pintype "bidirectional"))
      (node (ref "U3") (pin "40") (pinfunction "A17_40") (pintype "input"))
    )
    (net (code "100") (name "/XA18") (class "Default")
      (node (ref "U1") (pin "P142") (pinfunction "IO_L2P_0_P142") (pintype "bidirectional"))
      (node (ref "U3") (pin "41") (pinfunction "A18/NC_41") (pintype "input"))
    )
    (net (code "101") (name "/XA19") (class "Default")
      (node (ref "U1") (pin "P105") (pinfunction "IO_L1P_1_P105") (pintype "bidirectional"))
      (node (ref "U3") (pin "25") (pinfunction "A19/NC_25") (pintype "input"))
    )
    (net (code "102") (name "/XA20") (class "Default")
      (node (ref "U1") (pin "P143") (pinfunction "IO_L1N_VREF_0_P143") (pintype "bidirectional"))
      (node (ref "U3") (pin "42") (pinfunction "A20/NC_42") (pintype "input"))
    )
    (net (code "103") (name "/XD0") (class "Default")
      (node (ref "U1") (pin "P132") (pinfunction "IO_L35P_GCLK17_0_P132") (pintype "bidirectional"))
      (node (ref "U3") (pin "9") (pinfunction "D0_9") (pintype "bidirectional"))
    )
    (net (code "104") (name "/XD1") (class "Default")
      (node (ref "U1") (pin "P127") (pinfunction "IO_L36P_GCLK15_0_P127") (pintype "bidirectional"))
      (node (ref "U3") (pin "10") (pinfunction "D1_10") (pintype "bidirectional"))
    )
    (net (code "105") (name "/XD2") (class "Default")
      (node (ref "U1") (pin "P124") (pinfunction "IO_L37P_GCLK13_0_P124") (pintype "bidirectional"))
      (node (ref "U3") (pin "13") (pinfunction "D2_13") (pintype "bidirectional"))
    )
    (net (code "106") (name "/XD3") (class "Default")
      (node (ref "U1") (pin "P123") (pinfunction "IO_L37N_GCLK12_0_P123") (pintype "bidirectional"))
      (node (ref "U3") (pin "14") (pinfunction "D3_14") (pintype "bidirectional"))
    )
    (net (code "107") (name "/XD4") (class "Default")
      (node (ref "U1") (pin "P115") (pinfunction "IO_L65P_SCP3_0_P115") (pintype "bidirectional"))
      (node (ref "U3") (pin "31") (pinfunction "D4_31") (pintype "bidirectional"))
    )
    (net (code "108") (name "/XD5") (class "Default")
      (node (ref "U1") (pin "P117") (pinfunction "IO_L64P_SCP5_0_P117") (pintype "bidirectional"))
      (node (ref "U3") (pin "32") (pinfunction "D5_32") (pintype "bidirectional"))
    )
    (net (code "109") (name "/XD6") (class "Default")
      (node (ref "U1") (pin "P119") (pinfunction "IO_L63P_SCP7_0_P119") (pintype "bidirectional"))
      (node (ref "U3") (pin "35") (pinfunction "D6_35") (pintype "bidirectional"))
    )
    (net (code "110") (name "/XD7") (class "Default")
      (node (ref "U1") (pin "P126") (pinfunction "IO_L36N_GCLK14_0_P126") (pintype "bidirectional"))
      (node (ref "U3") (pin "36") (pinfunction "D7_36") (pintype "bidirectional"))
    )
    (net (code "111") (name "1.2V") (class "Default")
      (node (ref "C10") (pin "2") (pinfunction "2_2") (pintype "passive"))
      (node (ref "C11") (pin "2") (pinfunction "2_2") (pintype "passive"))
      (node (ref "C12") (pin "2") (pinfunction "2_2") (pintype "passive"))
      (node (ref "C13") (pin "2") (pinfunction "2_2") (pintype "passive"))
      (node (ref "C9") (pin "2") (pinfunction "2_2") (pintype "passive"))
      (node (ref "L2") (pin "2") (pinfunction "2_2") (pintype "passive"))
      (node (ref "U1") (pin "P128") (pinfunction "VCCINT_P128") (pintype "input"))
      (node (ref "U1") (pin "P19") (pinfunction "VCCINT_P19") (pintype "input"))
      (node (ref "U1") (pin "P28") (pinfunction "VCCINT_P28") (pintype "input"))
      (node (ref "U1") (pin "P52") (pinfunction "VCCINT_P52") (pintype "input"))
      (node (ref "U1") (pin "P89") (pinfunction "VCCINT_P89") (pintype "input"))
    )
    (net (code "112") (name "3.3V") (class "Default")
      (node (ref "C14") (pin "2") (pinfunction "2_2") (pintype "passive"))
      (node (ref "C15") (pin "2") (pinfunction "2_2") (pintype "passive"))
      (node (ref "C16") (pin "2") (pinfunction "2_2") (pintype "passive"))
      (node (ref "C17") (pin "2") (pinfunction "2_2") (pintype "passive"))
      (node (ref "C18") (pin "2") (pinfunction "2_2") (pintype "passive"))
      (node (ref "C19") (pin "2") (pinfunction "2_2") (pintype "passive"))
      (node (ref "C20") (pin "2") (pinfunction "2_2") (pintype "passive"))
      (node (ref "C21") (pin "2") (pinfunction "2_2") (pintype "passive"))
      (node (ref "C22") (pin "2") (pinfunction "2_2") (pintype "passive"))
      (node (ref "C23") (pin "2") (pinfunction "2_2") (pintype "passive"))
      (node (ref "C24") (pin "2") (pinfunction "2_2") (pintype "passive"))
      (node (ref "C25") (pin "2") (pinfunction "2_2") (pintype "passive"))
      (node (ref "C26") (pin "1") (pinfunction "1_1") (pintype "passive"))
      (node (ref "C27") (pin "2") (pinfunction "2_2") (pintype "passive"))
      (node (ref "J11") (pin "1") (pinfunction "1_1") (pintype "passive"))
      (node (ref "J12") (pin "12") (pinfunction "12_12") (pintype "passive"))
      (node (ref "JTAG") (pin "1") (pinfunction "1_1") (pintype "passive"))
      (node (ref "L1") (pin "2") (pinfunction "2_2") (pintype "passive"))
      (node (ref "R24") (pin "2") (pinfunction "2_2") (pintype "passive"))
      (node (ref "R27") (pin "2") (pinfunction "2_2") (pintype "passive"))
      (node (ref "R30") (pin "1") (pinfunction "1_1") (pintype "passive"))
      (node (ref "R31") (pin "2") (pinfunction "2_2") (pintype "passive"))
      (node (ref "R32") (pin "2") (pinfunction "2_2") (pintype "passive"))
      (node (ref "RGB") (pin "4") (pinfunction "S_4") (pintype "passive"))
      (node (ref "SDCARD") (pin "4") (pinfunction "VDD_4") (pintype "power_in"))
      (node (ref "U1") (pin "P103") (pinfunction "VCCO_1_P103") (pintype "input"))
      (node (ref "U1") (pin "P122") (pinfunction "VCCO_0_P122") (pintype "input"))
      (node (ref "U1") (pin "P125") (pinfunction "VCCO_0_P125") (pintype "input"))
      (node (ref "U1") (pin "P129") (pinfunction "VCCAUX_P129") (pintype "input"))
      (node (ref "U1") (pin "P135") (pinfunction "VCCO_0_P135") (pintype "input"))
      (node (ref "U1") (pin "P18") (pinfunction "VCCO_3_P18") (pintype "input"))
      (node (ref "U1") (pin "P20") (pinfunction "VCCAUX_P20") (pintype "input"))
      (node (ref "U1") (pin "P31") (pinfunction "VCCO_3_P31") (pintype "input"))
      (node (ref "U1") (pin "P36") (pinfunction "VCCAUX_P36") (pintype "input"))
      (node (ref "U1") (pin "P4") (pinfunction "VCCO_3_P4") (pintype "input"))
      (node (ref "U1") (pin "P42") (pinfunction "VCCO_2_P42") (pintype "input"))
      (node (ref "U1") (pin "P53") (pinfunction "VCCAUX_P53") (pintype "input"))
      (node (ref "U1") (pin "P63") (pinfunction "VCCO_2_P63") (pintype "input"))
      (node (ref "U1") (pin "P69") (pinfunction "IO_L1N_M0_CMPMISO_2_P69") (pintype "bidirectional"))
      (node (ref "U1") (pin "P76") (pinfunction "VCCO_1_P76") (pintype "input"))
      (node (ref "U1") (pin "P86") (pinfunction "VCCO_1_P86") (pintype "input"))
      (node (ref "U1") (pin "P90") (pinfunction "VCCAUX_P90") (pintype "input"))
      (node (ref "U2") (pin "8") (pinfunction "VCC_8") (pintype "bidirectional"))
      (node (ref "U3") (pin "11") (pinfunction "VDD_11") (pintype "input"))
      (node (ref "U3") (pin "33") (pinfunction "VDD_33") (pintype "input"))
      (node (ref "U5") (pin "4") (pinfunction "VCC_4") (pintype "power_in"))
    )
    (net (code "113") (name "5V") (class "Default")
      (node (ref "C28") (pin "1") (pinfunction "1_1") (pintype "passive"))
      (node (ref "C30") (pin "1") (pinfunction "1_1") (pintype "passive"))
      (node (ref "C32") (pin "2") (pinfunction "2_2") (pintype "passive"))
      (node (ref "C33") (pin "2") (pinfunction "2_2") (pintype "passive"))
      (node (ref "J12") (pin "1") (pinfunction "1_1") (pintype "passive"))
      (node (ref "KEYB") (pin "3") (pinfunction "3_3") (pintype "passive"))
      (node (ref "L3") (pin "2") (pinfunction "2_2") (pintype "passive"))
      (node (ref "PS/2") (pin "4") (pinfunction "4_4") (pintype "passive"))
      (node (ref "R5") (pin "1") (pinfunction "1_1") (pintype "passive"))
      (node (ref "R7") (pin "2") (pinfunction "2_2") (pintype "passive"))
      (node (ref "U4") (pin "14") (pinfunction "DPOS_14") (pintype "bidirectional"))
      (node (ref "U4") (pin "15") (pinfunction "VSYNC_15") (pintype "bidirectional"))
      (node (ref "U4") (pin "4") (pinfunction "APOS_4") (pintype "bidirectional"))
      (node (ref "U4") (pin "5") (pinfunction "CE_5") (pintype "bidirectional"))
      (node (ref "U6") (pin "3") (pinfunction "VIN_3") (pintype "input"))
      (node (ref "U7") (pin "3") (pinfunction "VIN_3") (pintype "input"))
    )
    (net (code "114") (name "GND") (class "Default")
      (node (ref "AUDIO") (pin "SLEEVE") (pinfunction "SLEEVE_SLEEVE") (pintype "bidirectional"))
      (node (ref "C1") (pin "2") (pinfunction "2_2") (pintype "passive"))
      (node (ref "C10") (pin "1") (pinfunction "1_1") (pintype "passive"))
      (node (ref "C11") (pin "1") (pinfunction "1_1") (pintype "passive"))
      (node (ref "C12") (pin "1") (pinfunction "1_1") (pintype "passive"))
      (node (ref "C13") (pin "1") (pinfunction "1_1") (pintype "passive"))
      (node (ref "C14") (pin "1") (pinfunction "1_1") (pintype "passive"))
      (node (ref "C15") (pin "1") (pinfunction "1_1") (pintype "passive"))
      (node (ref "C16") (pin "1") (pinfunction "1_1") (pintype "passive"))
      (node (ref "C17") (pin "1") (pinfunction "1_1") (pintype "passive"))
      (node (ref "C18") (pin "1") (pinfunction "1_1") (pintype "passive"))
      (node (ref "C19") (pin "1") (pinfunction "1_1") (pintype "passive"))
      (node (ref "C2") (pin "2") (pinfunction "2_2") (pintype "passive"))
      (node (ref "C20") (pin "1") (pinfunction "1_1") (pintype "passive"))
      (node (ref "C21") (pin "1") (pinfunction "1_1") (pintype "passive"))
      (node (ref "C22") (pin "1") (pinfunction "1_1") (pintype "passive"))
      (node (ref "C23") (pin "1") (pinfunction "1_1") (pintype "passive"))
      (node (ref "C24") (pin "1") (pinfunction "1_1") (pintype "passive"))
      (node (ref "C25") (pin "1") (pinfunction "1_1") (pintype "passive"))
      (node (ref "C26") (pin "2") (pinfunction "2_2") (pintype "passive"))
      (node (ref "C27") (pin "1") (pinfunction "1_1") (pintype "passive"))
      (node (ref "C28") (pin "2") (pinfunction "2_2") (pintype "passive"))
      (node (ref "C29") (pin "2") (pinfunction "2_2") (pintype "passive"))
      (node (ref "C3") (pin "2") (pinfunction "2_2") (pintype "passive"))
      (node (ref "C30") (pin "2") (pinfunction "2_2") (pintype "passive"))
      (node (ref "C31") (pin "2") (pinfunction "2_2") (pintype "passive"))
      (node (ref "C32") (pin "1") (pinfunction "1_1") (pintype "passive"))
      (node (ref "C33") (pin "1") (pinfunction "1_1") (pintype "passive"))
      (node (ref "C4") (pin "2") (pinfunction "2_2") (pintype "passive"))
      (node (ref "C9") (pin "1") (pinfunction "1_1") (pintype "passive"))
      (node (ref "CVBS") (pin "GND") (pinfunction "GND_GND") (pintype "passive"))
      (node (ref "D1") (pin "A") (pinfunction "A_A") (pintype "passive"))
      (node (ref "D2") (pin "C") (pinfunction "C_C") (pintype "passive"))
      (node (ref "D3") (pin "C") (pinfunction "C_C") (pintype "passive"))
      (node (ref "D4") (pin "C") (pinfunction "C_C") (pintype "passive"))
      (node (ref "D5") (pin "C") (pinfunction "C_C") (pintype "passive"))
      (node (ref "EAR") (pin "SLEEVE") (pinfunction "SLEEVE_SLEEVE") (pintype "bidirectional"))
      (node (ref "J10") (pin "12") (pinfunction "12_12") (pintype "passive"))
      (node (ref "J11") (pin "12") (pinfunction "12_12") (pintype "passive"))
      (node (ref "JOY") (pin "8") (pinfunction "8_8") (pintype "passive"))
      (node (ref "JTAG") (pin "2") (pinfunction "2_2") (pintype "passive"))
      (node (ref "PS/2") (pin "3") (pinfunction "3_3") (pintype "passive"))
      (node (ref "PWCON") (pin "1") (pinfunction "1_1") (pintype "passive"))
      (node (ref "PWUSB") (pin "5") (pinfunction "GND_5") (pintype "bidirectional"))
      (node (ref "R1") (pin "2") (pinfunction "2_2") (pintype "passive"))
      (node (ref "R2") (pin "2") (pinfunction "2_2") (pintype "passive"))
      (node (ref "R29") (pin "2") (pinfunction "2_2") (pintype "passive"))
      (node (ref "R3") (pin "2") (pinfunction "2_2") (pintype "passive"))
      (node (ref "RGB") (pin "1") (pinfunction "S_1") (pintype "passive"))
      (node (ref "RST") (pin "1") (pinfunction "1_1") (pintype "passive"))
      (node (ref "SDCARD") (pin "3") (pinfunction "VSS1_3") (pintype "power_in"))
      (node (ref "SDCARD") (pin "6") (pinfunction "VSS2_6") (pintype "power_in"))
      (node (ref "SDCARD") (pin "M1") (pinfunction "GND_M1") (pintype "power_in"))
      (node (ref "SDCARD") (pin "M2") (pinfunction "GND_M2") (pintype "power_in"))
      (node (ref "SDCARD") (pin "M3") (pinfunction "GND_M3") (pintype "power_in"))
      (node (ref "SDCARD") (pin "M4") (pinfunction "GND_M4") (pintype "power_in"))
      (node (ref "T1") (pin "2") (pinfunction "E_2") (pintype "passive"))
      (node (ref "U1") (pin "P108") (pinfunction "GND_P108") (pintype "power_in"))
      (node (ref "U1") (pin "P113") (pinfunction "GND_P113") (pintype "power_in"))
      (node (ref "U1") (pin "P13") (pinfunction "GND_P13") (pintype "power_in"))
      (node (ref "U1") (pin "P130") (pinfunction "GND_P130") (pintype "power_in"))
      (node (ref "U1") (pin "P136") (pinfunction "GND_P136") (pintype "power_in"))
      (node (ref "U1") (pin "P144") (pinfunction "IO_L1P_HSWAPEN_0_P144") (pintype "bidirectional"))
      (node (ref "U1") (pin "P25") (pinfunction "GND_P25") (pintype "power_in"))
      (node (ref "U1") (pin "P3") (pinfunction "GND_P3") (pintype "power_in"))
      (node (ref "U1") (pin "P49") (pinfunction "GND_P49") (pintype "power_in"))
      (node (ref "U1") (pin "P54") (pinfunction "GND_P54") (pintype "power_in"))
      (node (ref "U1") (pin "P60") (pinfunction "IO_L13P_M1_2_P60") (pintype "bidirectional"))
      (node (ref "U1") (pin "P68") (pinfunction "GND_P68") (pintype "power_in"))
      (node (ref "U1") (pin "P73") (pinfunction "SUSPEND_P73") (pintype "input"))
      (node (ref "U1") (pin "P77") (pinfunction "GND_P77") (pintype "power_in"))
      (node (ref "U1") (pin "P91") (pinfunction "GND_P91") (pintype "power_in"))
      (node (ref "U1") (pin "P96") (pinfunction "GND_P96") (pintype "power_in"))
      (node (ref "U2") (pin "4") (pinfunction "GND_4") (pintype "bidirectional"))
      (node (ref "U3") (pin "12") (pinfunction "VSS_12") (pintype "input"))
      (node (ref "U3") (pin "34") (pinfunction "VSS_34") (pintype "input"))
      (node (ref "U3") (pin "37") (pinfunction "~{OE}_37") (pintype "input"))
      (node (ref "U3") (pin "8") (pinfunction "~{CS}_8") (pintype "input"))
      (node (ref "U4") (pin "12") (pinfunction "YTRAP_12") (pintype "bidirectional"))
      (node (ref "U4") (pin "13") (pinfunction "DGND_13") (pintype "bidirectional"))
      (node (ref "U4") (pin "2") (pinfunction "AGND_2") (pintype "bidirectional"))
      (node (ref "U5") (pin "2") (pinfunction "GND_2") (pintype "power_in"))
      (node (ref "U6") (pin "1") (pinfunction "GND_1") (pintype "power_in"))
      (node (ref "U7") (pin "1") (pinfunction "GND_1") (pintype "power_in"))
    )
    (net (code "115") (name "Net-(C2-Pad1)") (class "Default")
      (node (ref "C2") (pin "1") (pinfunction "1_1") (pintype "passive"))
      (node (ref "C5") (pin "1") (pinfunction "1_1") (pintype "passive"))
      (node (ref "D1") (pin "C") (pinfunction "C_C") (pintype "passive"))
      (node (ref "R28") (pin "1") (pinfunction "1_1") (pintype "passive"))
    )
    (net (code "116") (name "Net-(C3-Pad1)") (class "Default")
      (node (ref "C3") (pin "1") (pinfunction "1_1") (pintype "passive"))
      (node (ref "C35") (pin "1") (pinfunction "1_1") (pintype "passive"))
      (node (ref "R23") (pin "1") (pinfunction "1_1") (pintype "passive"))
    )
    (net (code "117") (name "Net-(C5-Pad2)") (class "Default")
      (node (ref "C5") (pin "2") (pinfunction "2_2") (pintype "passive"))
      (node (ref "R15") (pin "2") (pinfunction "2_2") (pintype "passive"))
    )
    (net (code "118") (name "Net-(C34-Pad1)") (class "Default")
      (node (ref "C34") (pin "1") (pinfunction "1_1") (pintype "passive"))
      (node (ref "C4") (pin "1") (pinfunction "1_1") (pintype "passive"))
      (node (ref "R22") (pin "1") (pinfunction "1_1") (pintype "passive"))
    )
    (net (code "119") (name "Net-(C36-Pad-)") (class "Default")
      (node (ref "C36") (pin "-") (pinfunction "-_-") (pintype "passive"))
      (node (ref "R4") (pin "1") (pinfunction "1_1") (pintype "passive"))
    )
    (net (code "120") (name "Net-(CVBS-PadSIG)") (class "Default")
      (node (ref "CVBS") (pin "SIG") (pinfunction "SIG_SIG") (pintype "passive"))
      (node (ref "R4") (pin "2") (pinfunction "2_2") (pintype "passive"))
    )
    (net (code "121") (name "Net-(D2-PadA)") (class "Default")
      (node (ref "D2") (pin "A") (pinfunction "A_A") (pintype "passive"))
      (node (ref "R25") (pin "2") (pinfunction "2_2") (pintype "passive"))
      (node (ref "Y1") (pin "1") (pinfunction "1_1") (pintype "passive"))
    )
    (net (code "122") (name "Net-(D3-PadA)") (class "Default")
      (node (ref "D3") (pin "A") (pinfunction "A_A") (pintype "passive"))
      (node (ref "R26") (pin "1") (pinfunction "1_1") (pintype "passive"))
      (node (ref "Y2") (pin "1") (pinfunction "1_1") (pintype "passive"))
    )
    (net (code "123") (name "Net-(D4-PadA)") (class "Default")
      (node (ref "D4") (pin "A") (pinfunction "A_A") (pintype "passive"))
      (node (ref "R6") (pin "1") (pinfunction "1_1") (pintype "passive"))
    )
    (net (code "124") (name "Net-(D5-PadA)") (class "Default")
      (node (ref "D5") (pin "A") (pinfunction "A_A") (pintype "passive"))
      (node (ref "R7") (pin "1") (pinfunction "1_1") (pintype "passive"))
    )
    (net (code "125") (name "Net-(EAR-LEFT)") (class "Default")
      (node (ref "EAR") (pin "TIP") (pinfunction "LEFT_TIP") (pintype "bidirectional"))
      (node (ref "R15") (pin "1") (pinfunction "1_1") (pintype "passive"))
      (node (ref "R29") (pin "1") (pinfunction "1_1") (pintype "passive"))
    )
    (net (code "126") (name "Net-(JOY-Pad7)") (class "Default")
      (node (ref "JOY") (pin "7") (pinfunction "7_7") (pintype "passive"))
      (node (ref "R5") (pin "2") (pinfunction "2_2") (pintype "passive"))
    )
    (net (code "127") (name "Net-(L3-Pad1)") (class "Default")
      (node (ref "L3") (pin "1") (pinfunction "1_1") (pintype "passive"))
      (node (ref "SW") (pin "1") (pinfunction "1_1") (pintype "passive"))
    )
    (net (code "128") (name "Net-(PS/2-Pad2)") (class "Default")
      (node (ref "PS/2") (pin "2") (pinfunction "2_2") (pintype "passive"))
      (node (ref "R9") (pin "1") (pinfunction "1_1") (pintype "passive"))
    )
    (net (code "129") (name "Net-(PS/2-Pad6)") (class "Default")
      (node (ref "PS/2") (pin "6") (pinfunction "6_6") (pintype "passive"))
      (node (ref "R11") (pin "1") (pinfunction "1_1") (pintype "passive"))
    )
    (net (code "130") (name "Net-(PWUSB-VCC)") (class "Default")
      (node (ref "PWCON") (pin "2") (pinfunction "2_2") (pintype "passive"))
      (node (ref "PWUSB") (pin "1") (pinfunction "VCC_1") (pintype "bidirectional"))
      (node (ref "SW") (pin "2") (pinfunction "2_2") (pintype "passive"))
    )
    (net (code "131") (name "Net-(SDCARD-DAT1)") (class "Default")
      (node (ref "R31") (pin "1") (pinfunction "1_1") (pintype "passive"))
      (node (ref "SDCARD") (pin "8") (pinfunction "DAT1_8") (pintype "bidirectional"))
    )
    (net (code "132") (name "Net-(SDCARD-DAT2)") (class "Default")
      (node (ref "R32") (pin "1") (pinfunction "1_1") (pintype "passive"))
      (node (ref "SDCARD") (pin "9") (pinfunction "DAT2_9") (pintype "bidirectional"))
    )
    (net (code "133") (name "Net-(T1-B)") (class "Default")
      (node (ref "R28") (pin "2") (pinfunction "2_2") (pintype "passive"))
      (node (ref "T1") (pin "1") (pinfunction "B_1") (pintype "passive"))
    )
    (net (code "134") (name "Net-(U1C-PROGRAM_B_2)") (class "Default")
      (node (ref "R24") (pin "1") (pinfunction "1_1") (pintype "passive"))
      (node (ref "RST") (pin "2") (pinfunction "2_2") (pintype "passive"))
      (node (ref "U1") (pin "P37") (pinfunction "PROGRAM_B_2_P37") (pintype "input"))
    )
    (net (code "135") (name "Net-(U4-4FSC)") (class "Default")
      (node (ref "C1") (pin "1") (pinfunction "1_1") (pintype "passive"))
      (node (ref "U4") (pin "3") (pinfunction "4FSC_3") (pintype "bidirectional"))
      (node (ref "Y1") (pin "2") (pinfunction "2_2") (pintype "passive"))
      (node (ref "Y2") (pin "2") (pinfunction "2_2") (pintype "passive"))
    )
    (net (code "136") (name "Net-(U4-BIN)") (class "Default")
      (node (ref "C8") (pin "1") (pinfunction "1_1") (pintype "passive"))
      (node (ref "U4") (pin "8") (pinfunction "BIN_8") (pintype "bidirectional"))
    )
    (net (code "137") (name "Net-(U4-COMP)") (class "Default")
      (node (ref "C36") (pin "+") (pinfunction "+_+") (pintype "passive"))
      (node (ref "U4") (pin "10") (pinfunction "COMP_10") (pintype "bidirectional"))
    )
    (net (code "138") (name "Net-(U4-GIN)") (class "Default")
      (node (ref "C7") (pin "1") (pinfunction "1_1") (pintype "passive"))
      (node (ref "U4") (pin "7") (pinfunction "GIN_7") (pintype "bidirectional"))
    )
    (net (code "139") (name "Net-(U4-RIN)") (class "Default")
      (node (ref "C6") (pin "1") (pinfunction "1_1") (pintype "passive"))
      (node (ref "U4") (pin "6") (pinfunction "RIN_6") (pintype "bidirectional"))
    )
    (net (code "140") (name "Net-(U6-VOUT)") (class "Default")
      (node (ref "C29") (pin "1") (pinfunction "1_1") (pintype "passive"))
      (node (ref "L1") (pin "1") (pinfunction "1_1") (pintype "passive"))
      (node (ref "U6") (pin "2") (pinfunction "VOUT_2") (pintype "output"))
    )
    (net (code "141") (name "Net-(U7-VOUT)") (class "Default")
      (node (ref "C31") (pin "1") (pinfunction "1_1") (pintype "passive"))
      (node (ref "L2") (pin "1") (pinfunction "1_1") (pintype "passive"))
      (node (ref "U7") (pin "2") (pinfunction "VOUT_2") (pintype "output"))
    )
    (net (code "142") (name "unconnected-(EAR-RIGHT-PadRING)") (class "Default")
      (node (ref "EAR") (pin "RING") (pinfunction "RIGHT_RING") (pintype "bidirectional"))
    )
    (net (code "143") (name "unconnected-(J10-Pad11)") (class "Default")
      (node (ref "J10") (pin "11") (pinfunction "11_11") (pintype "passive"))
    )
    (net (code "144") (name "unconnected-(PWUSB-D+-Pad3)") (class "Default")
      (node (ref "PWUSB") (pin "3") (pinfunction "D+_3") (pintype "bidirectional"))
    )
    (net (code "145") (name "unconnected-(PWUSB-D--Pad2)") (class "Default")
      (node (ref "PWUSB") (pin "2") (pinfunction "D-_2") (pintype "bidirectional"))
    )
    (net (code "146") (name "unconnected-(PWUSB-ID-Pad4)") (class "Default")
      (node (ref "PWUSB") (pin "4") (pinfunction "ID_4") (pintype "bidirectional"))
    )
    (net (code "147") (name "unconnected-(PWUSB-SHIELD-Pad6)") (class "Default")
      (node (ref "PWUSB") (pin "6") (pinfunction "SHIELD_6") (pintype "bidirectional"))
    )
    (net (code "148") (name "unconnected-(SDCARD-CDI#-Pad10)") (class "Default")
      (node (ref "SDCARD") (pin "10") (pinfunction "CDI#_10") (pintype "output"))
    )
    (net (code "149") (name "unconnected-(SDCARD-WP-Pad11)") (class "Default")
      (node (ref "SDCARD") (pin "11") (pinfunction "WP_11") (pintype "output"))
    )
    (net (code "150") (name "unconnected-(U1C-CMPCS_B_2-PadP72)") (class "Default")
      (node (ref "U1") (pin "P72") (pinfunction "CMPCS_B_2_P72") (pintype "bidirectional"))
    )
    (net (code "151") (name "unconnected-(U1C-DONE_2-PadP71)") (class "Default")
      (node (ref "U1") (pin "P71") (pinfunction "DONE_2_P71") (pintype "bidirectional"))
    )
    (net (code "152") (name "unconnected-(U4-CRMA-Pad9)") (class "Default")
      (node (ref "U4") (pin "9") (pinfunction "CRMA_9") (pintype "bidirectional"))
    )
    (net (code "153") (name "unconnected-(U4-LUMA-Pad11)") (class "Default")
      (node (ref "U4") (pin "11") (pinfunction "LUMA_11") (pintype "bidirectional"))
    )
    (net (code "154") (name "unconnected-(U5-E{slash}D-Pad1)") (class "Default")
      (node (ref "U5") (pin "1") (pinfunction "E/D_1") (pintype "input"))
    )
  )
)
